# Board_Connector_Template.net
KiCad netlist of a schematic drawn in Altium Designer
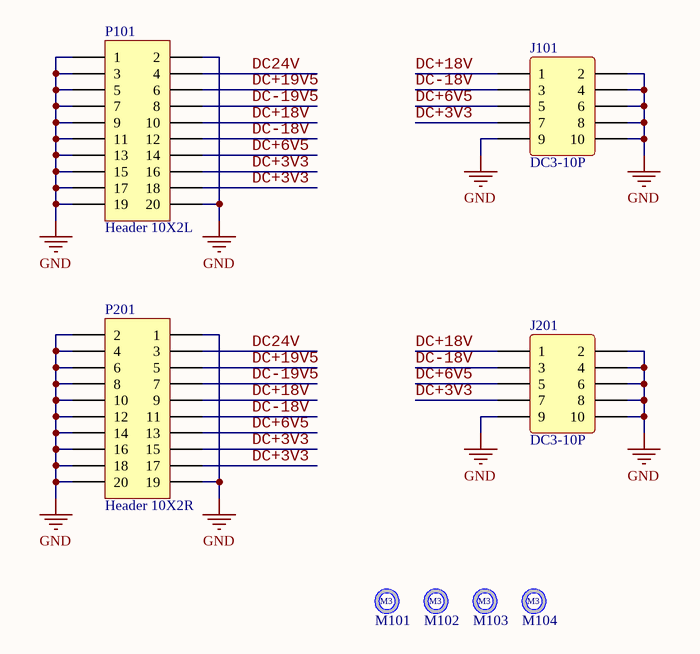
[diagram p0: Board Connector Template.SchDoc]

(export (version "E")
  (design (tool "Eeschema 10.0.6"))
  (components
    (comp (ref "J101")
      (value "DC3-10P")
      (footprint "DC3-10P")
      (libsource (lib "carrot_lib") (part "DC3-10P"))
    )
    (comp (ref "J201")
      (value "DC3-10P")
      (footprint "DC3-10P")
      (libsource (lib "carrot_lib") (part "DC3-10P"))
    )
    (comp (ref "M101") (value "M3") (footprint "M3-3.2X5") (libsource (lib "carrot_lib") (part "M3")))
    (comp (ref "M102") (value "M3") (footprint "M3-3.2X5") (libsource (lib "carrot_lib") (part "M3")))
    (comp (ref "M103") (value "M3") (footprint "M3-3.2X5") (libsource (lib "carrot_lib") (part "M3")))
    (comp (ref "M104") (value "M3") (footprint "M3-3.2X5") (libsource (lib "carrot_lib") (part "M3")))
    (comp (ref "P101")
      (value "Header 10X2L")
      (footprint "HDR2X10LML")
      (description "Header, 10-Pin, Dual row, Pin 1 on Left")
      (libsource (lib "carrot_lib") (part "Header 10X2L"))
    )
    (comp (ref "P201")
      (value "Header 10X2R")
      (footprint "HDR2X10LFR")
      (description "Header, 10-Pin, Dual row, Pin 1 on Right")
      (libsource (lib "carrot_lib") (part "Header 10X2R"))
    )
  )
  (nets
    (net (code "1") (name "/DC+3V3") (class "Default")
      (node (ref "J101") (pin "7") (pinfunction "7_7") (pintype "passive"))
      (node (ref "J201") (pin "7") (pinfunction "7_7") (pintype "passive"))
      (node (ref "P101") (pin "16") (pinfunction "16_16") (pintype "passive"))
      (node (ref "P101") (pin "18") (pinfunction "18_18") (pintype "passive"))
      (node (ref "P201") (pin "15") (pinfunction "15_15") (pintype "passive"))
      (node (ref "P201") (pin "17") (pinfunction "17_17") (pintype "passive"))
    )
    (net (code "2") (name "/DC+6V5") (class "Default")
      (node (ref "J101") (pin "5") (pinfunction "5_5") (pintype "passive"))
      (node (ref "J201") (pin "5") (pinfunction "5_5") (pintype "passive"))
      (node (ref "P101") (pin "14") (pinfunction "14_14") (pintype "passive"))
      (node (ref "P201") (pin "13") (pinfunction "13_13") (pintype "passive"))
    )
    (net (code "3") (name "/DC+18V") (class "Default")
      (node (ref "J101") (pin "1") (pinfunction "1_1") (pintype "passive"))
      (node (ref "J201") (pin "1") (pinfunction "1_1") (pintype "passive"))
      (node (ref "P101") (pin "10") (pinfunction "10_10") (pintype "passive"))
      (node (ref "P201") (pin "9") (pinfunction "9_9") (pintype "passive"))
    )
    (net (code "4") (name "/DC+19V5") (class "Default")
      (node (ref "P101") (pin "6") (pinfunction "6_6") (pintype "passive"))
      (node (ref "P201") (pin "5") (pinfunction "5_5") (pintype "passive"))
    )
    (net (code "5") (name "/DC-18V") (class "Default")
      (node (ref "J101") (pin "3") (pinfunction "3_3") (pintype "passive"))
      (node (ref "J201") (pin "3") (pinfunction "3_3") (pintype "passive"))
      (node (ref "P101") (pin "12") (pinfunction "12_12") (pintype "passive"))
      (node (ref "P201") (pin "11") (pinfunction "11_11") (pintype "passive"))
    )
    (net (code "6") (name "/DC-19V5") (class "Default")
      (node (ref "P101") (pin "8") (pinfunction "8_8") (pintype "passive"))
      (node (ref "P201") (pin "7") (pinfunction "7_7") (pintype "passive"))
    )
    (net (code "7") (name "/DC24V") (class "Default")
      (node (ref "P101") (pin "4") (pinfunction "4_4") (pintype "passive"))
      (node (ref "P201") (pin "3") (pinfunction "3_3") (pintype "passive"))
    )
    (net (code "8") (name "GND") (class "Default")
      (node (ref "J101") (pin "10") (pinfunction "10_10") (pintype "passive"))
      (node (ref "J101") (pin "2") (pinfunction "2_2") (pintype "passive"))
      (node (ref "J101") (pin "4") (pinfunction "4_4") (pintype "passive"))
      (node (ref "J101") (pin "6") (pinfunction "6_6") (pintype "passive"))
      (node (ref "J101") (pin "8") (pinfunction "8_8") (pintype "passive"))
      (node (ref "J101") (pin "9") (pinfunction "9_9") (pintype "passive"))
      (node (ref "J201") (pin "10") (pinfunction "10_10") (pintype "passive"))
      (node (ref "J201") (pin "2") (pinfunction "2_2") (pintype "passive"))
      (node (ref "J201") (pin "4") (pinfunction "4_4") (pintype "passive"))
      (node (ref "J201") (pin "6") (pinfunction "6_6") (pintype "passive"))
      (node (ref "J201") (pin "8") (pinfunction "8_8") (pintype "passive"))
      (node (ref "J201") (pin "9") (pinfunction "9_9") (pintype "passive"))
      (node (ref "P101") (pin "1") (pinfunction "1_1") (pintype "passive"))
      (node (ref "P101") (pin "11") (pinfunction "11_11") (pintype "passive"))
      (node (ref "P101") (pin "13") (pinfunction "13_13") (pintype "passive"))
      (node (ref "P101") (pin "15") (pinfunction "15_15") (pintype "passive"))
      (node (ref "P101") (pin "17") (pinfunction "17_17") (pintype "passive"))
      (node (ref "P101") (pin "19") (pinfunction "19_19") (pintype "passive"))
      (node (ref "P101") (pin "2") (pinfunction "2_2") (pintype "passive"))
      (node (ref "P101") (pin "20") (pinfunction "20_20") (pintype "passive"))
      (node (ref "P101") (pin "3") (pinfunction "3_3") (pintype "passive"))
      (node (ref "P101") (pin "5") (pinfunction "5_5") (pintype "passive"))
      (node (ref "P101") (pin "7") (pinfunction "7_7") (pintype "passive"))
      (node (ref "P101") (pin "9") (pinfunction "9_9") (pintype "passive"))
      (node (ref "P201") (pin "1") (pinfunction "1_1") (pintype "passive"))
      (node (ref "P201") (pin "10") (pinfunction "10_10") (pintype "passive"))
      (node (ref "P201") (pin "12") (pinfunction "12_12") (pintype "passive"))
      (node (ref "P201") (pin "14") (pinfunction "14_14") (pintype "passive"))
      (node (ref "P201") (pin "16") (pinfunction "16_16") (pintype "passive"))
      (node (ref "P201") (pin "18") (pinfunction "18_18") (pintype "passive"))
      (node (ref "P201") (pin "19") (pinfunction "19_19") (pintype "passive"))
      (node (ref "P201") (pin "2") (pinfunction "2_2") (pintype "passive"))
      (node (ref "P201") (pin "20") (pinfunction "20_20") (pintype "passive"))
      (node (ref "P201") (pin "4") (pinfunction "4_4") (pintype "passive"))
      (node (ref "P201") (pin "6") (pinfunction "6_6") (pintype "passive"))
      (node (ref "P201") (pin "8") (pinfunction "8_8") (pintype "passive"))
    )
  )
)
